# MPU.net
KiCad netlist of a schematic drawn in Altium Designer
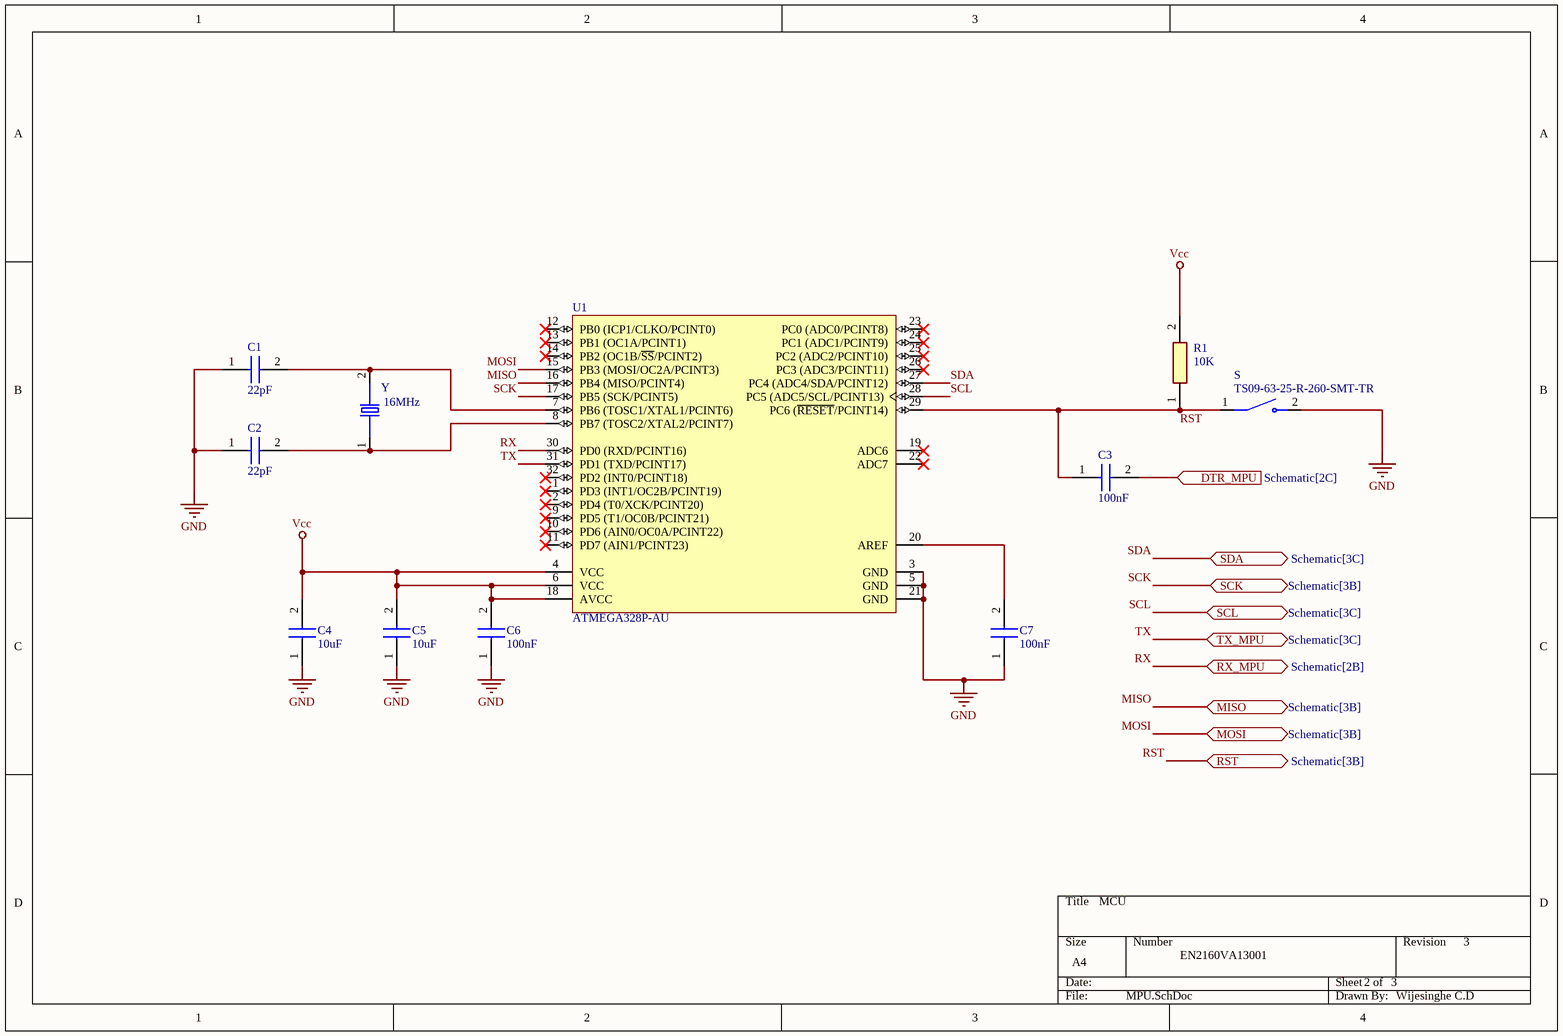
[diagram p0: MPU.SchDoc]

(export (version "E")
  (design (tool "Eeschema 10.0.6"))
  (components
    (comp (ref "C1")
      (value "22pF")
      (footprint "SamacSys:C0805")
      (description "Capacitor")
      (fields
        (field (name "MANUFACTURER_PART_NUMBER") "C0805X220J1GACTU")
        (field (name "MOUSER PART NUMBER") "80-C0805X220J1GACTU")
      )
      (libsource (lib "*") (part "C0805X220J1GACTU"))
    )
    (comp (ref "C2")
      (value "22pF")
      (footprint "SamacSys:C0805")
      (description "Capacitor")
      (fields
        (field (name "MANUFACTURER_PART_NUMBER") "C0805X220J1GACTU")
        (field (name "MOUSER PART NUMBER") "80-C0805X220J1GACTU")
      )
      (libsource (lib "*") (part "C0805X220J1GACTU"))
    )
    (comp (ref "C3")
      (value "100nF")
      (footprint "SamacSys:CAPC2013X137N")
      (description "Capacitor")
      (fields
        (field (name "MANUFACTURER_PART_NUMBER") "0805B104K500NT")
        (field (name "MOUSER PART NUMBER") "767-0805B104K500NT")
      )
      (libsource (lib "*") (part "0805B104K500NT"))
    )
    (comp (ref "C4")
      (value "10uF")
      (footprint "SamacSys:CAPC2012X145N")
      (description "Capacitor")
      (fields
        (field (name "MANUFACTURER_PART_NUMBER") "GCM21BC71E106KE36K")
        (field (name "MOUSER PART NUMBER") "81-GCM21B71E106KE36K")
      )
      (libsource (lib "*") (part "GCM21BC71E106KE36K"))
    )
    (comp (ref "C5")
      (value "10uF")
      (footprint "SamacSys:CAPC2012X145N")
      (description "Capacitor")
      (fields
        (field (name "MANUFACTURER_PART_NUMBER") "GCM21BC71E106KE36K")
        (field (name "MOUSER PART NUMBER") "81-GCM21B71E106KE36K")
      )
      (libsource (lib "*") (part "GCM21BC71E106KE36K"))
    )
    (comp (ref "C6")
      (value "100nF")
      (footprint "SamacSys:CAPC2013X137N")
      (description "Capacitor")
      (fields
        (field (name "MANUFACTURER_PART_NUMBER") "0805B104K500NT")
        (field (name "MOUSER PART NUMBER") "767-0805B104K500NT")
      )
      (libsource (lib "*") (part "0805B104K500NT"))
    )
    (comp (ref "C7")
      (value "100nF")
      (footprint "SamacSys:CAPC2013X137N")
      (description "Capacitor")
      (fields
        (field (name "MANUFACTURER_PART_NUMBER") "0805B104K500NT")
        (field (name "MOUSER PART NUMBER") "767-0805B104K500NT")
      )
      (libsource (lib "*") (part "0805B104K500NT"))
    )
    (comp (ref "R1")
      (value "10K")
      (footprint "SamacSys:RESC2013X65N")
      (description "Resistor")
      (fields (field (name "MANUFACTURER_PART_NUMBER") "0805W8F1002T5E"))
      (libsource (lib "*") (part "0805W8F1002T5E"))
    )
    (comp (ref "S")
      (value "TS09-63-25-R-260-SMT-TR")
      (footprint "SW_TS09-63-25-R-260-SMT-TR")
      (libsource (lib "TS09-63-25-R-260-SMT-TR") (part "TS09-63-25-R-260-SMT-TR"))
    )
    (comp (ref "U1")
      (value "ATMEGA328P-AU")
      (footprint "ATML-32A_M")
      (fields (field (name "MANUFACTURER") "Atmel"))
      (libsource (lib "My files") (part "ATML-ATMEGAX8A-32A"))
    )
    (comp (ref "Y")
      (value "16MHz")
      (footprint "XTAL_FOXSDLF/160-20")
      (description "Microprocessor, Crystal; 16 Mhz; + 30 Ppm @ Degc; 7 Pf (Max.); 20 Pf; -20 Deg")
      (fields (field (name "MF") "Fox Electronics") (field (name "MP") "FOXSDLF/160-20"))
      (libsource (lib "FOXSDLF_160-20") (part "FOXSDLF/160-20"))
    )
  )
  (nets
    (net (code "1") (name "/DTR_MPU") (class "Default")
      (node (ref "C3") (pin "2") (pinfunction "2_2") (pintype "passive"))
    )
    (net (code "2") (name "/MISO") (class "Default")
      (node (ref "U1") (pin "16") (pinfunction "PB4_(MISO/PCINT4)_16") (pintype "bidirectional"))
    )
    (net (code "3") (name "/MOSI") (class "Default")
      (node (ref "U1") (pin "15") (pinfunction "PB3_(MOSI/OC2A/PCINT3)_15") (pintype "bidirectional"))
    )
    (net (code "4") (name "/RST") (class "Default")
      (node (ref "C3") (pin "1") (pinfunction "1_1") (pintype "passive"))
      (node (ref "R1") (pin "1") (pinfunction "1_1") (pintype "passive"))
      (node (ref "S") (pin "1") (pinfunction "1_1") (pintype "passive"))
      (node (ref "U1") (pin "29") (pinfunction "PC6_(~{RESET}/PCINT14)_29") (pintype "bidirectional"))
    )
    (net (code "5") (name "/RX") (class "Default")
      (node (ref "U1") (pin "30") (pinfunction "PD0_(RXD/PCINT16)_30") (pintype "bidirectional"))
    )
    (net (code "6") (name "/SCK") (class "Default")
      (node (ref "U1") (pin "17") (pinfunction "PB5_(SCK/PCINT5)_17") (pintype "bidirectional"))
    )
    (net (code "7") (name "/SCL") (class "Default")
      (node (ref "U1") (pin "28") (pinfunction "PC5_(ADC5/SCL/PCINT13)_28") (pintype "bidirectional"))
    )
    (net (code "8") (name "/SDA") (class "Default")
      (node (ref "U1") (pin "27") (pinfunction "PC4_(ADC4/SDA/PCINT12)_27") (pintype "bidirectional"))
    )
    (net (code "9") (name "/TX") (class "Default")
      (node (ref "U1") (pin "31") (pinfunction "PD1_(TXD/PCINT17)_31") (pintype "bidirectional"))
    )
    (net (code "10") (name "GND") (class "Default")
      (node (ref "C1") (pin "1") (pinfunction "1_1") (pintype "passive"))
      (node (ref "C2") (pin "1") (pinfunction "1_1") (pintype "passive"))
      (node (ref "C4") (pin "1") (pinfunction "1_1") (pintype "passive"))
      (node (ref "C5") (pin "1") (pinfunction "1_1") (pintype "passive"))
      (node (ref "C6") (pin "1") (pinfunction "1_1") (pintype "passive"))
      (node (ref "C7") (pin "1") (pinfunction "1_1") (pintype "passive"))
      (node (ref "S") (pin "2") (pinfunction "2_2") (pintype "passive"))
      (node (ref "U1") (pin "21") (pinfunction "GND_21") (pintype "power_in"))
      (node (ref "U1") (pin "3") (pinfunction "GND_3") (pintype "power_in"))
      (node (ref "U1") (pin "5") (pinfunction "GND_5") (pintype "power_in"))
    )
    (net (code "11") (name "Net-(U1-AREF)") (class "Default")
      (node (ref "C7") (pin "2") (pinfunction "2_2") (pintype "passive"))
      (node (ref "U1") (pin "20") (pinfunction "AREF_20") (pintype "passive"))
    )
    (net (code "12") (name "Net-(U1-PB6_(TOSC1{slash}XTAL1{slash}PCINT6))") (class "Default")
      (node (ref "C1") (pin "2") (pinfunction "2_2") (pintype "passive"))
      (node (ref "U1") (pin "7") (pinfunction "PB6_(TOSC1/XTAL1/PCINT6)_7") (pintype "bidirectional"))
      (node (ref "Y") (pin "2") (pinfunction "2_2") (pintype "passive"))
    )
    (net (code "13") (name "Net-(U1-PB7_(TOSC2{slash}XTAL2{slash}PCINT7))") (class "Default")
      (node (ref "C2") (pin "2") (pinfunction "2_2") (pintype "passive"))
      (node (ref "U1") (pin "8") (pinfunction "PB7_(TOSC2/XTAL2/PCINT7)_8") (pintype "bidirectional"))
      (node (ref "Y") (pin "1") (pinfunction "1_1") (pintype "passive"))
    )
    (net (code "14") (name "Vcc") (class "Default")
      (node (ref "C4") (pin "2") (pinfunction "2_2") (pintype "passive"))
      (node (ref "C5") (pin "2") (pinfunction "2_2") (pintype "passive"))
      (node (ref "C6") (pin "2") (pinfunction "2_2") (pintype "passive"))
      (node (ref "R1") (pin "2") (pinfunction "2_2") (pintype "passive"))
      (node (ref "U1") (pin "18") (pinfunction "AVCC_18") (pintype "power_in"))
      (node (ref "U1") (pin "4") (pinfunction "VCC_4") (pintype "power_in"))
      (node (ref "U1") (pin "6") (pinfunction "VCC_6") (pintype "power_in"))
    )
    (net (code "15") (name "unconnected-(U1-ADC6-Pad19)") (class "Default")
      (node (ref "U1") (pin "19") (pinfunction "ADC6_19") (pintype "passive+no_connect"))
    )
    (net (code "16") (name "unconnected-(U1-ADC7-Pad22)") (class "Default")
      (node (ref "U1") (pin "22") (pinfunction "ADC7_22") (pintype "passive+no_connect"))
    )
    (net (code "17") (name "unconnected-(U1-PB0_(ICP1{slash}CLKO{slash}PCINT0)-Pad12)") (class "Default")
      (node (ref "U1") (pin "12") (pinfunction "PB0_(ICP1/CLKO/PCINT0)_12") (pintype "bidirectional+no_connect"))
    )
    (net (code "18") (name "unconnected-(U1-PB1_(OC1A{slash}PCINT1)-Pad13)") (class "Default")
      (node (ref "U1") (pin "13") (pinfunction "PB1_(OC1A/PCINT1)_13") (pintype "bidirectional+no_connect"))
    )
    (net (code "19") (name "unconnected-(U1-PB2_(OC1B{slash}~{SS}{slash}PCINT2)-Pad14)") (class "Default")
      (node (ref "U1") (pin "14") (pinfunction "PB2_(OC1B/~{SS}/PCINT2)_14") (pintype "bidirectional+no_connect"))
    )
    (net (code "20") (name "unconnected-(U1-PC0_(ADC0{slash}PCINT8)-Pad23)") (class "Default")
      (node (ref "U1") (pin "23") (pinfunction "PC0_(ADC0/PCINT8)_23") (pintype "bidirectional+no_connect"))
    )
    (net (code "21") (name "unconnected-(U1-PC1_(ADC1{slash}PCINT9)-Pad24)") (class "Default")
      (node (ref "U1") (pin "24") (pinfunction "PC1_(ADC1/PCINT9)_24") (pintype "bidirectional+no_connect"))
    )
    (net (code "22") (name "unconnected-(U1-PC2_(ADC2{slash}PCINT10)-Pad25)") (class "Default")
      (node (ref "U1") (pin "25") (pinfunction "PC2_(ADC2/PCINT10)_25") (pintype "bidirectional+no_connect"))
    )
    (net (code "23") (name "unconnected-(U1-PC3_(ADC3{slash}PCINT11)-Pad26)") (class "Default")
      (node (ref "U1") (pin "26") (pinfunction "PC3_(ADC3/PCINT11)_26") (pintype "bidirectional+no_connect"))
    )
    (net (code "24") (name "unconnected-(U1-PD2_(INT0{slash}PCINT18)-Pad32)") (class "Default")
      (node (ref "U1") (pin "32") (pinfunction "PD2_(INT0/PCINT18)_32") (pintype "bidirectional+no_connect"))
    )
    (net (code "25") (name "unconnected-(U1-PD3_(INT1{slash}OC2B{slash}PCINT19)-Pad1)") (class "Default")
      (node (ref "U1") (pin "1") (pinfunction "PD3_(INT1/OC2B/PCINT19)_1") (pintype "bidirectional+no_connect"))
    )
    (net (code "26") (name "unconnected-(U1-PD4_(T0{slash}XCK{slash}PCINT20)-Pad2)") (class "Default")
      (node (ref "U1") (pin "2") (pinfunction "PD4_(T0/XCK/PCINT20)_2") (pintype "bidirectional+no_connect"))
    )
    (net (code "27") (name "unconnected-(U1-PD5_(T1{slash}OC0B{slash}PCINT21)-Pad9)") (class "Default")
      (node (ref "U1") (pin "9") (pinfunction "PD5_(T1/OC0B/PCINT21)_9") (pintype "bidirectional+no_connect"))
    )
    (net (code "28") (name "unconnected-(U1-PD6_(AIN0{slash}OC0A{slash}PCINT22)-Pad10)") (class "Default")
      (node (ref "U1") (pin "10") (pinfunction "PD6_(AIN0/OC0A/PCINT22)_10") (pintype "bidirectional+no_connect"))
    )
    (net (code "29") (name "unconnected-(U1-PD7_(AIN1{slash}PCINT23)-Pad11)") (class "Default")
      (node (ref "U1") (pin "11") (pinfunction "PD7_(AIN1/PCINT23)_11") (pintype "bidirectional+no_connect"))
    )
  )
)
